# TDC_cern.net
KiCad netlist of a schematic drawn in Altium Designer
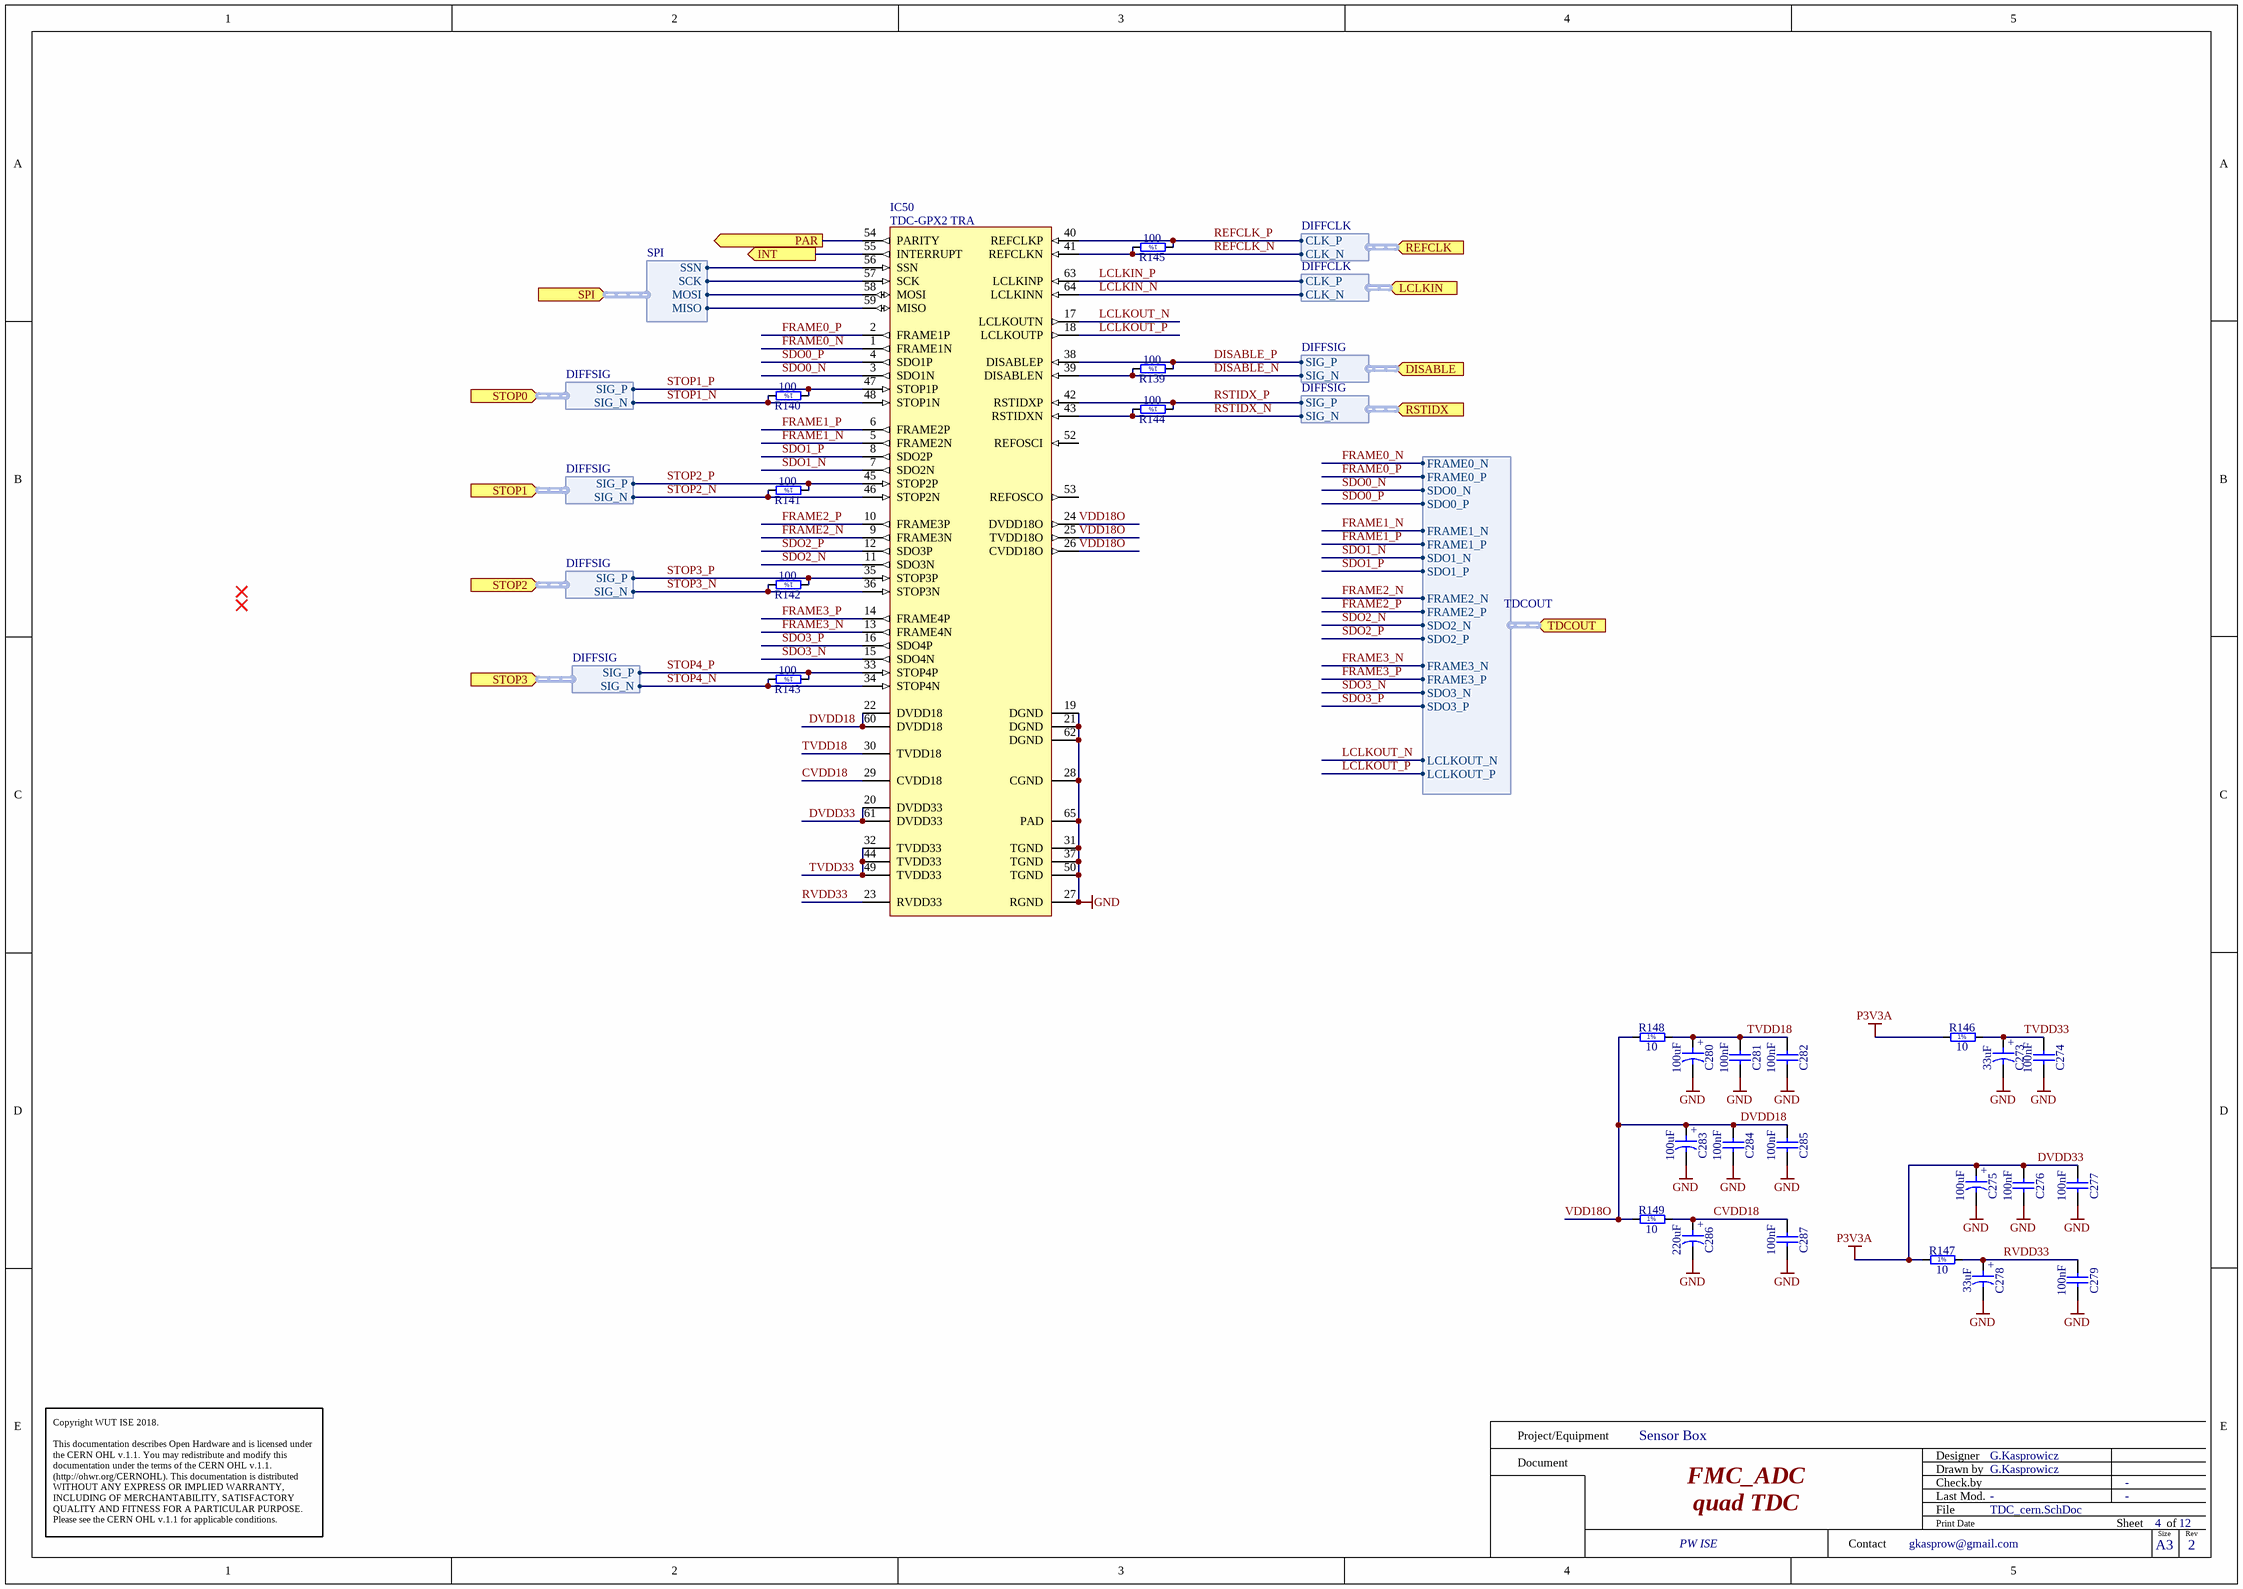
[diagram p0: TDC_cern.SchDoc]

(export (version "E")
  (design (tool "Eeschema 10.0.6"))
  (components
    (comp (ref "C273")
      (value "33uF")
      (footprint "CAPMP3216X180N")
      (description "Polarised capacitor")
      (fields
        (field (name "PART NUMBER") "CTE3216-18_33UF_4V_10%")
        (field (name "VOLTAGE") "4V")
        (field (name "AUTHOR") "CERN DEM JLC")
      )
      (libsource (lib "Capacitors") (part "Capacitor - polarized"))
    )
    (comp (ref "C274")
      (value "100nF")
      (footprint "CAPC0603X33N")
      (description "Non-polarised capacitor")
      (fields
        (field (name "PART NUMBER") "CC0201_100NF_6.3V_10%_X5R")
        (field (name "VOLTAGE") "6.3V")
        (field (name "AUTHOR") "CERN DEM JLC")
      )
      (libsource (lib "Capacitors") (part "Capacitor - non polarized"))
    )
    (comp (ref "C275")
      (value "100uF")
      (footprint "CAPMP3216X180N")
      (description "Polarised capacitor")
      (fields
        (field (name "PART NUMBER") "CTE3216-18_100UF_6.3V_20%_ESR0500_AVX_TLJ")
        (field (name "VOLTAGE") "6.3V")
        (field (name "AUTHOR") "CERN DEM JLC")
      )
      (libsource (lib "Capacitors") (part "Capacitor - polarized"))
    )
    (comp (ref "C276")
      (value "100nF")
      (footprint "CAPC0603X33N")
      (description "Non-polarised capacitor")
      (fields
        (field (name "PART NUMBER") "CC0201_100NF_6.3V_10%_X5R")
        (field (name "VOLTAGE") "6.3V")
        (field (name "AUTHOR") "CERN DEM JLC")
      )
      (libsource (lib "Capacitors") (part "Capacitor - non polarized"))
    )
    (comp (ref "C277")
      (value "100nF")
      (footprint "CAPC0603X33N")
      (description "Non-polarised capacitor")
      (fields
        (field (name "PART NUMBER") "CC0201_100NF_6.3V_10%_X5R")
        (field (name "VOLTAGE") "6.3V")
        (field (name "AUTHOR") "CERN DEM JLC")
      )
      (libsource (lib "Capacitors") (part "Capacitor - non polarized"))
    )
    (comp (ref "C278")
      (value "33uF")
      (footprint "CAPMP3216X180N")
      (description "Polarised capacitor")
      (fields
        (field (name "PART NUMBER") "CTE3216-18_33UF_4V_10%")
        (field (name "VOLTAGE") "4V")
        (field (name "AUTHOR") "CERN DEM JLC")
      )
      (libsource (lib "Capacitors") (part "Capacitor - polarized"))
    )
    (comp (ref "C279")
      (value "100nF")
      (footprint "CAPC0603X33N")
      (description "Non-polarised capacitor")
      (fields
        (field (name "PART NUMBER") "CC0201_100NF_6.3V_10%_X5R")
        (field (name "VOLTAGE") "6.3V")
        (field (name "AUTHOR") "CERN DEM JLC")
      )
      (libsource (lib "Capacitors") (part "Capacitor - non polarized"))
    )
    (comp (ref "C280")
      (value "100uF")
      (footprint "CAPMP3216X180N")
      (description "Polarised capacitor")
      (fields
        (field (name "PART NUMBER") "CTE3216-18_100UF_6.3V_20%_ESR0500_AVX_TLJ")
        (field (name "VOLTAGE") "6.3V")
        (field (name "AUTHOR") "CERN DEM JLC")
      )
      (libsource (lib "Capacitors") (part "Capacitor - polarized"))
    )
    (comp (ref "C281")
      (value "100nF")
      (footprint "CAPC0603X33N")
      (description "Non-polarised capacitor")
      (fields
        (field (name "PART NUMBER") "CC0201_100NF_6.3V_10%_X5R")
        (field (name "VOLTAGE") "6.3V")
        (field (name "AUTHOR") "CERN DEM JLC")
      )
      (libsource (lib "Capacitors") (part "Capacitor - non polarized"))
    )
    (comp (ref "C282")
      (value "100nF")
      (footprint "CAPC0603X33N")
      (description "Non-polarised capacitor")
      (fields
        (field (name "PART NUMBER") "CC0201_100NF_6.3V_10%_X5R")
        (field (name "VOLTAGE") "6.3V")
        (field (name "AUTHOR") "CERN DEM JLC")
      )
      (libsource (lib "Capacitors") (part "Capacitor - non polarized"))
    )
    (comp (ref "C283")
      (value "100uF")
      (footprint "CAPMP3216X180N")
      (description "Polarised capacitor")
      (fields
        (field (name "PART NUMBER") "CTE3216-18_100UF_6.3V_20%_ESR0500_AVX_TLJ")
        (field (name "VOLTAGE") "6.3V")
        (field (name "AUTHOR") "CERN DEM JLC")
      )
      (libsource (lib "Capacitors") (part "Capacitor - polarized"))
    )
    (comp (ref "C284")
      (value "100nF")
      (footprint "CAPC0603X33N")
      (description "Non-polarised capacitor")
      (fields
        (field (name "PART NUMBER") "CC0201_100NF_6.3V_10%_X5R")
        (field (name "VOLTAGE") "6.3V")
        (field (name "AUTHOR") "CERN DEM JLC")
      )
      (libsource (lib "Capacitors") (part "Capacitor - non polarized"))
    )
    (comp (ref "C285")
      (value "100nF")
      (footprint "CAPC0603X33N")
      (description "Non-polarised capacitor")
      (fields
        (field (name "PART NUMBER") "CC0201_100NF_6.3V_10%_X5R")
        (field (name "VOLTAGE") "6.3V")
        (field (name "AUTHOR") "CERN DEM JLC")
      )
      (libsource (lib "Capacitors") (part "Capacitor - non polarized"))
    )
    (comp (ref "C286")
      (value "220uF")
      (footprint "CAPMP3528X210N")
      (description "Polarised capacitor")
      (fields
        (field (name "PART NUMBER") "CTE3528-21_220UF_2.5V_10%")
        (field (name "VOLTAGE") "2.5V")
        (field (name "AUTHOR") "CERN DEM JLC")
      )
      (libsource (lib "Capacitors") (part "Capacitor - polarized"))
    )
    (comp (ref "C287")
      (value "100nF")
      (footprint "CAPC0603X33N")
      (description "Non-polarised capacitor")
      (fields
        (field (name "PART NUMBER") "CC0201_100NF_6.3V_10%_X5R")
        (field (name "VOLTAGE") "6.3V")
        (field (name "AUTHOR") "CERN DEM JLC")
      )
      (libsource (lib "Capacitors") (part "Capacitor - non polarized"))
    )
    (comp (ref "IC50")
      (value "TDC-GPX2 TRA")
      (footprint "QFN50P900X900X100-65N-S615")
      (description "4 Channel Time to Digital Converter")
      (fields (field (name "MANUFACTURER") "AMS") (field (name "AUTHOR") "GK"))
      (libsource (lib "LIBRARY_SCH") (part "TDC-GPX2_QFN"))
    )
    (comp (ref "R139")
      (value "100")
      (footprint "RESC0603X28N")
      (description "Resistor - 1%")
      (fields
        (field (name "PART NUMBER") "R0201_100R_1%_0.05W_200PPM")
        (field (name "POWER") "0.05W")
        (field (name "AUTHOR") "CERN DEM JLC")
      )
      (libsource (lib "Resistors") (part "Resistor - 1%"))
    )
    (comp (ref "R140")
      (value "100")
      (footprint "RESC0603X28N")
      (description "Resistor - 1%")
      (fields
        (field (name "PART NUMBER") "R0201_100R_1%_0.05W_200PPM")
        (field (name "POWER") "0.05W")
        (field (name "AUTHOR") "CERN DEM JLC")
      )
      (libsource (lib "Resistors") (part "Resistor - 1%"))
    )
    (comp (ref "R141")
      (value "100")
      (footprint "RESC0603X28N")
      (description "Resistor - 1%")
      (fields
        (field (name "PART NUMBER") "R0201_100R_1%_0.05W_200PPM")
        (field (name "POWER") "0.05W")
        (field (name "AUTHOR") "CERN DEM JLC")
      )
      (libsource (lib "Resistors") (part "Resistor - 1%"))
    )
    (comp (ref "R142")
      (value "100")
      (footprint "RESC0603X28N")
      (description "Resistor - 1%")
      (fields
        (field (name "PART NUMBER") "R0201_100R_1%_0.05W_200PPM")
        (field (name "POWER") "0.05W")
        (field (name "AUTHOR") "CERN DEM JLC")
      )
      (libsource (lib "Resistors") (part "Resistor - 1%"))
    )
    (comp (ref "R143")
      (value "100")
      (footprint "RESC0603X28N")
      (description "Resistor - 1%")
      (fields
        (field (name "PART NUMBER") "R0201_100R_1%_0.05W_200PPM")
        (field (name "POWER") "0.05W")
        (field (name "AUTHOR") "CERN DEM JLC")
      )
      (libsource (lib "Resistors") (part "Resistor - 1%"))
    )
    (comp (ref "R144")
      (value "100")
      (footprint "RESC0603X28N")
      (description "Resistor - 1%")
      (fields
        (field (name "PART NUMBER") "R0201_100R_1%_0.05W_200PPM")
        (field (name "POWER") "0.05W")
        (field (name "AUTHOR") "CERN DEM JLC")
      )
      (libsource (lib "Resistors") (part "Resistor - 1%"))
    )
    (comp (ref "R145")
      (value "100")
      (footprint "RESC0603X28N")
      (description "Resistor - 1%")
      (fields
        (field (name "PART NUMBER") "R0201_100R_1%_0.05W_200PPM")
        (field (name "POWER") "0.05W")
        (field (name "AUTHOR") "CERN DEM JLC")
      )
      (libsource (lib "Resistors") (part "Resistor - 1%"))
    )
    (comp (ref "R146")
      (value "10")
      (footprint "RESC1005X40N")
      (description "Resistor - 1%")
      (fields
        (field (name "PART NUMBER") "R0402_10R_1%_0.0625W_200PPM")
        (field (name "POWER") "0.0625W")
        (field (name "AUTHOR") "CERN DEM JLC")
      )
      (libsource (lib "Resistors") (part "Resistor - 1%"))
    )
    (comp (ref "R147")
      (value "10")
      (footprint "RESC1005X40N")
      (description "Resistor - 1%")
      (fields
        (field (name "PART NUMBER") "R0402_10R_1%_0.0625W_200PPM")
        (field (name "POWER") "0.0625W")
        (field (name "AUTHOR") "CERN DEM JLC")
      )
      (libsource (lib "Resistors") (part "Resistor - 1%"))
    )
    (comp (ref "R148")
      (value "10")
      (footprint "RESC1005X40N")
      (description "Resistor - 1%")
      (fields
        (field (name "PART NUMBER") "R0402_10R_1%_0.0625W_200PPM")
        (field (name "POWER") "0.0625W")
        (field (name "AUTHOR") "CERN DEM JLC")
      )
      (libsource (lib "Resistors") (part "Resistor - 1%"))
    )
    (comp (ref "R149")
      (value "10")
      (footprint "RESC1005X40N")
      (description "Resistor - 1%")
      (fields
        (field (name "PART NUMBER") "R0402_10R_1%_0.0625W_200PPM")
        (field (name "POWER") "0.0625W")
        (field (name "AUTHOR") "CERN DEM JLC")
      )
      (libsource (lib "Resistors") (part "Resistor - 1%"))
    )
  )
  (nets
    (net (code "5") (name "/CVDD18") (class "Default")
      (node (ref "C286") (pin "1") (pinfunction "1_1") (pintype "passive"))
      (node (ref "C287") (pin "1") (pinfunction "1_1") (pintype "passive"))
      (node (ref "IC50") (pin "29") (pinfunction "CVDD18_29") (pintype "power_in"))
      (node (ref "R149") (pin "2") (pinfunction "2_2") (pintype "passive"))
    )
    (net (code "6") (name "/DISABLE_N") (class "Default")
      (node (ref "IC50") (pin "39") (pinfunction "DISABLEN_39") (pintype "input"))
      (node (ref "R139") (pin "2") (pinfunction "2_2") (pintype "passive"))
    )
    (net (code "7") (name "/DISABLE_P") (class "Default")
      (node (ref "IC50") (pin "38") (pinfunction "DISABLEP_38") (pintype "input"))
      (node (ref "R139") (pin "1") (pinfunction "1_1") (pintype "passive"))
    )
    (net (code "8") (name "/DVDD18") (class "Default")
      (node (ref "C283") (pin "1") (pinfunction "1_1") (pintype "passive"))
      (node (ref "C284") (pin "1") (pinfunction "1_1") (pintype "passive"))
      (node (ref "C285") (pin "1") (pinfunction "1_1") (pintype "passive"))
      (node (ref "IC50") (pin "22") (pinfunction "DVDD18_22") (pintype "power_in"))
      (node (ref "IC50") (pin "24") (pinfunction "DVDD18O_24") (pintype "output"))
      (node (ref "IC50") (pin "25") (pinfunction "TVDD18O_25") (pintype "output"))
      (node (ref "IC50") (pin "26") (pinfunction "CVDD18O_26") (pintype "output"))
      (node (ref "IC50") (pin "60") (pinfunction "DVDD18_60") (pintype "power_in"))
      (node (ref "R148") (pin "1") (pinfunction "1_1") (pintype "passive"))
      (node (ref "R149") (pin "1") (pinfunction "1_1") (pintype "passive"))
    )
    (net (code "9") (name "/FRAME0_N") (class "Default")
      (node (ref "IC50") (pin "1") (pinfunction "FRAME1N_1") (pintype "output"))
    )
    (net (code "10") (name "/FRAME0_P") (class "Default")
      (node (ref "IC50") (pin "2") (pinfunction "FRAME1P_2") (pintype "output"))
    )
    (net (code "11") (name "/FRAME1_N") (class "Default")
      (node (ref "IC50") (pin "5") (pinfunction "FRAME2N_5") (pintype "output"))
    )
    (net (code "12") (name "/FRAME1_P") (class "Default")
      (node (ref "IC50") (pin "6") (pinfunction "FRAME2P_6") (pintype "output"))
    )
    (net (code "13") (name "/FRAME2_N") (class "Default")
      (node (ref "IC50") (pin "9") (pinfunction "FRAME3N_9") (pintype "output"))
    )
    (net (code "14") (name "/FRAME2_P") (class "Default")
      (node (ref "IC50") (pin "10") (pinfunction "FRAME3P_10") (pintype "output"))
    )
    (net (code "15") (name "/FRAME3_N") (class "Default")
      (node (ref "IC50") (pin "13") (pinfunction "FRAME4N_13") (pintype "output"))
    )
    (net (code "16") (name "/FRAME3_P") (class "Default")
      (node (ref "IC50") (pin "14") (pinfunction "FRAME4P_14") (pintype "output"))
    )
    (net (code "17") (name "/INT") (class "Default")
      (node (ref "IC50") (pin "55") (pinfunction "INTERRUPT_55") (pintype "output"))
    )
    (net (code "18") (name "/LCLKIN_N") (class "Default")
      (node (ref "IC50") (pin "64") (pinfunction "LCLKINN_64") (pintype "input"))
    )
    (net (code "19") (name "/LCLKIN_P") (class "Default")
      (node (ref "IC50") (pin "63") (pinfunction "LCLKINP_63") (pintype "input"))
    )
    (net (code "20") (name "/LCLKOUT_N") (class "Default")
      (node (ref "IC50") (pin "17") (pinfunction "LCLKOUTN_17") (pintype "output"))
    )
    (net (code "21") (name "/LCLKOUT_P") (class "Default")
      (node (ref "IC50") (pin "18") (pinfunction "LCLKOUTP_18") (pintype "output"))
    )
    (net (code "22") (name "/MISO") (class "Default")
      (node (ref "IC50") (pin "59") (pinfunction "MISO_59") (pintype "bidirectional"))
    )
    (net (code "23") (name "/MOSI") (class "Default")
      (node (ref "IC50") (pin "58") (pinfunction "MOSI_58") (pintype "bidirectional"))
    )
    (net (code "24") (name "/PAR") (class "Default")
      (node (ref "IC50") (pin "54") (pinfunction "PARITY_54") (pintype "output"))
    )
    (net (code "25") (name "/REFCLK_N") (class "Default")
      (node (ref "IC50") (pin "41") (pinfunction "REFCLKN_41") (pintype "input"))
      (node (ref "R145") (pin "2") (pinfunction "2_2") (pintype "passive"))
    )
    (net (code "26") (name "/REFCLK_P") (class "Default")
      (node (ref "IC50") (pin "40") (pinfunction "REFCLKP_40") (pintype "input"))
      (node (ref "R145") (pin "1") (pinfunction "1_1") (pintype "passive"))
    )
    (net (code "27") (name "/RSTIDX_N") (class "Default")
      (node (ref "IC50") (pin "43") (pinfunction "RSTIDXN_43") (pintype "input"))
      (node (ref "R144") (pin "2") (pinfunction "2_2") (pintype "passive"))
    )
    (net (code "28") (name "/RSTIDX_P") (class "Default")
      (node (ref "IC50") (pin "42") (pinfunction "RSTIDXP_42") (pintype "input"))
      (node (ref "R144") (pin "1") (pinfunction "1_1") (pintype "passive"))
    )
    (net (code "29") (name "/RVDD33") (class "Default")
      (node (ref "C278") (pin "1") (pinfunction "1_1") (pintype "passive"))
      (node (ref "C279") (pin "1") (pinfunction "1_1") (pintype "passive"))
      (node (ref "IC50") (pin "23") (pinfunction "RVDD33_23") (pintype "power_in"))
      (node (ref "R147") (pin "2") (pinfunction "2_2") (pintype "passive"))
    )
    (net (code "30") (name "/SCK") (class "Default")
      (node (ref "IC50") (pin "57") (pinfunction "SCK_57") (pintype "input"))
    )
    (net (code "31") (name "/SDO0_N") (class "Default")
      (node (ref "IC50") (pin "3") (pinfunction "SDO1N_3") (pintype "output"))
    )
    (net (code "32") (name "/SDO0_P") (class "Default")
      (node (ref "IC50") (pin "4") (pinfunction "SDO1P_4") (pintype "output"))
    )
    (net (code "33") (name "/SDO1_N") (class "Default")
      (node (ref "IC50") (pin "7") (pinfunction "SDO2N_7") (pintype "output"))
    )
    (net (code "34") (name "/SDO1_P") (class "Default")
      (node (ref "IC50") (pin "8") (pinfunction "SDO2P_8") (pintype "output"))
    )
    (net (code "35") (name "/SDO2_N") (class "Default")
      (node (ref "IC50") (pin "11") (pinfunction "SDO3N_11") (pintype "output"))
    )
    (net (code "36") (name "/SDO2_P") (class "Default")
      (node (ref "IC50") (pin "12") (pinfunction "SDO3P_12") (pintype "output"))
    )
    (net (code "37") (name "/SDO3_N") (class "Default")
      (node (ref "IC50") (pin "15") (pinfunction "SDO4N_15") (pintype "output"))
    )
    (net (code "38") (name "/SDO3_P") (class "Default")
      (node (ref "IC50") (pin "16") (pinfunction "SDO4P_16") (pintype "output"))
    )
    (net (code "39") (name "/SSN") (class "Default")
      (node (ref "IC50") (pin "56") (pinfunction "SSN_56") (pintype "input"))
    )
    (net (code "40") (name "/STOP1_N") (class "Default")
      (node (ref "IC50") (pin "48") (pinfunction "STOP1N_48") (pintype "input"))
      (node (ref "R140") (pin "2") (pinfunction "2_2") (pintype "passive"))
    )
    (net (code "41") (name "/STOP1_P") (class "Default")
      (node (ref "IC50") (pin "47") (pinfunction "STOP1P_47") (pintype "input"))
      (node (ref "R140") (pin "1") (pinfunction "1_1") (pintype "passive"))
    )
    (net (code "42") (name "/STOP2_N") (class "Default")
      (node (ref "IC50") (pin "46") (pinfunction "STOP2N_46") (pintype "input"))
      (node (ref "R141") (pin "2") (pinfunction "2_2") (pintype "passive"))
    )
    (net (code "43") (name "/STOP2_P") (class "Default")
      (node (ref "IC50") (pin "45") (pinfunction "STOP2P_45") (pintype "input"))
      (node (ref "R141") (pin "1") (pinfunction "1_1") (pintype "passive"))
    )
    (net (code "44") (name "/STOP3_N") (class "Default")
      (node (ref "IC50") (pin "36") (pinfunction "STOP3N_36") (pintype "input"))
      (node (ref "R142") (pin "2") (pinfunction "2_2") (pintype "passive"))
    )
    (net (code "45") (name "/STOP3_P") (class "Default")
      (node (ref "IC50") (pin "35") (pinfunction "STOP3P_35") (pintype "input"))
      (node (ref "R142") (pin "1") (pinfunction "1_1") (pintype "passive"))
    )
    (net (code "46") (name "/STOP4_N") (class "Default")
      (node (ref "IC50") (pin "34") (pinfunction "STOP4N_34") (pintype "input"))
      (node (ref "R143") (pin "2") (pinfunction "2_2") (pintype "passive"))
    )
    (net (code "47") (name "/STOP4_P") (class "Default")
      (node (ref "IC50") (pin "33") (pinfunction "STOP4P_33") (pintype "input"))
      (node (ref "R143") (pin "1") (pinfunction "1_1") (pintype "passive"))
    )
    (net (code "48") (name "/TVDD18") (class "Default")
      (node (ref "C280") (pin "1") (pinfunction "1_1") (pintype "passive"))
      (node (ref "C281") (pin "1") (pinfunction "1_1") (pintype "passive"))
      (node (ref "C282") (pin "1") (pinfunction "1_1") (pintype "passive"))
      (node (ref "IC50") (pin "30") (pinfunction "TVDD18_30") (pintype "power_in"))
      (node (ref "R148") (pin "2") (pinfunction "2_2") (pintype "passive"))
    )
    (net (code "49") (name "/TVDD33") (class "Default")
      (node (ref "C273") (pin "1") (pinfunction "1_1") (pintype "passive"))
      (node (ref "C274") (pin "1") (pinfunction "1_1") (pintype "passive"))
      (node (ref "IC50") (pin "32") (pinfunction "TVDD33_32") (pintype "power_in"))
      (node (ref "IC50") (pin "44") (pinfunction "TVDD33_44") (pintype "power_in"))
      (node (ref "IC50") (pin "49") (pinfunction "TVDD33_49") (pintype "power_in"))
      (node (ref "R146") (pin "2") (pinfunction "2_2") (pintype "passive"))
    )
    (net (code "54") (name "GND") (class "Default")
      (node (ref "C273") (pin "2") (pinfunction "2_2") (pintype "passive"))
      (node (ref "C274") (pin "2") (pinfunction "2_2") (pintype "passive"))
      (node (ref "C275") (pin "2") (pinfunction "2_2") (pintype "passive"))
      (node (ref "C276") (pin "2") (pinfunction "2_2") (pintype "passive"))
      (node (ref "C277") (pin "2") (pinfunction "2_2") (pintype "passive"))
      (node (ref "C278") (pin "2") (pinfunction "2_2") (pintype "passive"))
      (node (ref "C279") (pin "2") (pinfunction "2_2") (pintype "passive"))
      (node (ref "C280") (pin "2") (pinfunction "2_2") (pintype "passive"))
      (node (ref "C281") (pin "2") (pinfunction "2_2") (pintype "passive"))
      (node (ref "C282") (pin "2") (pinfunction "2_2") (pintype "passive"))
      (node (ref "C283") (pin "2") (pinfunction "2_2") (pintype "passive"))
      (node (ref "C284") (pin "2") (pinfunction "2_2") (pintype "passive"))
      (node (ref "C285") (pin "2") (pinfunction "2_2") (pintype "passive"))
      (node (ref "C286") (pin "2") (pinfunction "2_2") (pintype "passive"))
      (node (ref "C287") (pin "2") (pinfunction "2_2") (pintype "passive"))
      (node (ref "IC50") (pin "19") (pinfunction "DGND_19") (pintype "power_in"))
      (node (ref "IC50") (pin "21") (pinfunction "DGND_21") (pintype "power_in"))
      (node (ref "IC50") (pin "27") (pinfunction "RGND_27") (pintype "power_in"))
      (node (ref "IC50") (pin "28") (pinfunction "CGND_28") (pintype "power_in"))
      (node (ref "IC50") (pin "31") (pinfunction "TGND_31") (pintype "power_in"))
      (node (ref "IC50") (pin "37") (pinfunction "TGND_37") (pintype "power_in"))
      (node (ref "IC50") (pin "50") (pinfunction "TGND_50") (pintype "power_in"))
      (node (ref "IC50") (pin "62") (pinfunction "DGND_62") (pintype "power_in"))
      (node (ref "IC50") (pin "65") (pinfunction "PAD_65") (pintype "power_in"))
    )
    (net (code "55") (name "P3V3A") (class "Default")
      (node (ref "C275") (pin "1") (pinfunction "1_1") (pintype "passive"))
      (node (ref "C276") (pin "1") (pinfunction "1_1") (pintype "passive"))
      (node (ref "C277") (pin "1") (pinfunction "1_1") (pintype "passive"))
      (node (ref "IC50") (pin "20") (pinfunction "DVDD33_20") (pintype "power_in"))
      (node (ref "IC50") (pin "61") (pinfunction "DVDD33_61") (pintype "power_in"))
      (node (ref "R146") (pin "1") (pinfunction "1_1") (pintype "passive"))
      (node (ref "R147") (pin "1") (pinfunction "1_1") (pintype "passive"))
    )
    (net (code "56") (name "unconnected-(IC50-REFOSCI-Pad52)") (class "Default")
      (node (ref "IC50") (pin "52") (pinfunction "REFOSCI_52") (pintype "input"))
    )
    (net (code "57") (name "unconnected-(IC50-REFOSCO-Pad53)") (class "Default")
      (node (ref "IC50") (pin "53") (pinfunction "REFOSCO_53") (pintype "output"))
    )
  )
)
